# GB2530-K.net
KiCad netlist of a schematic drawn in Altium Designer
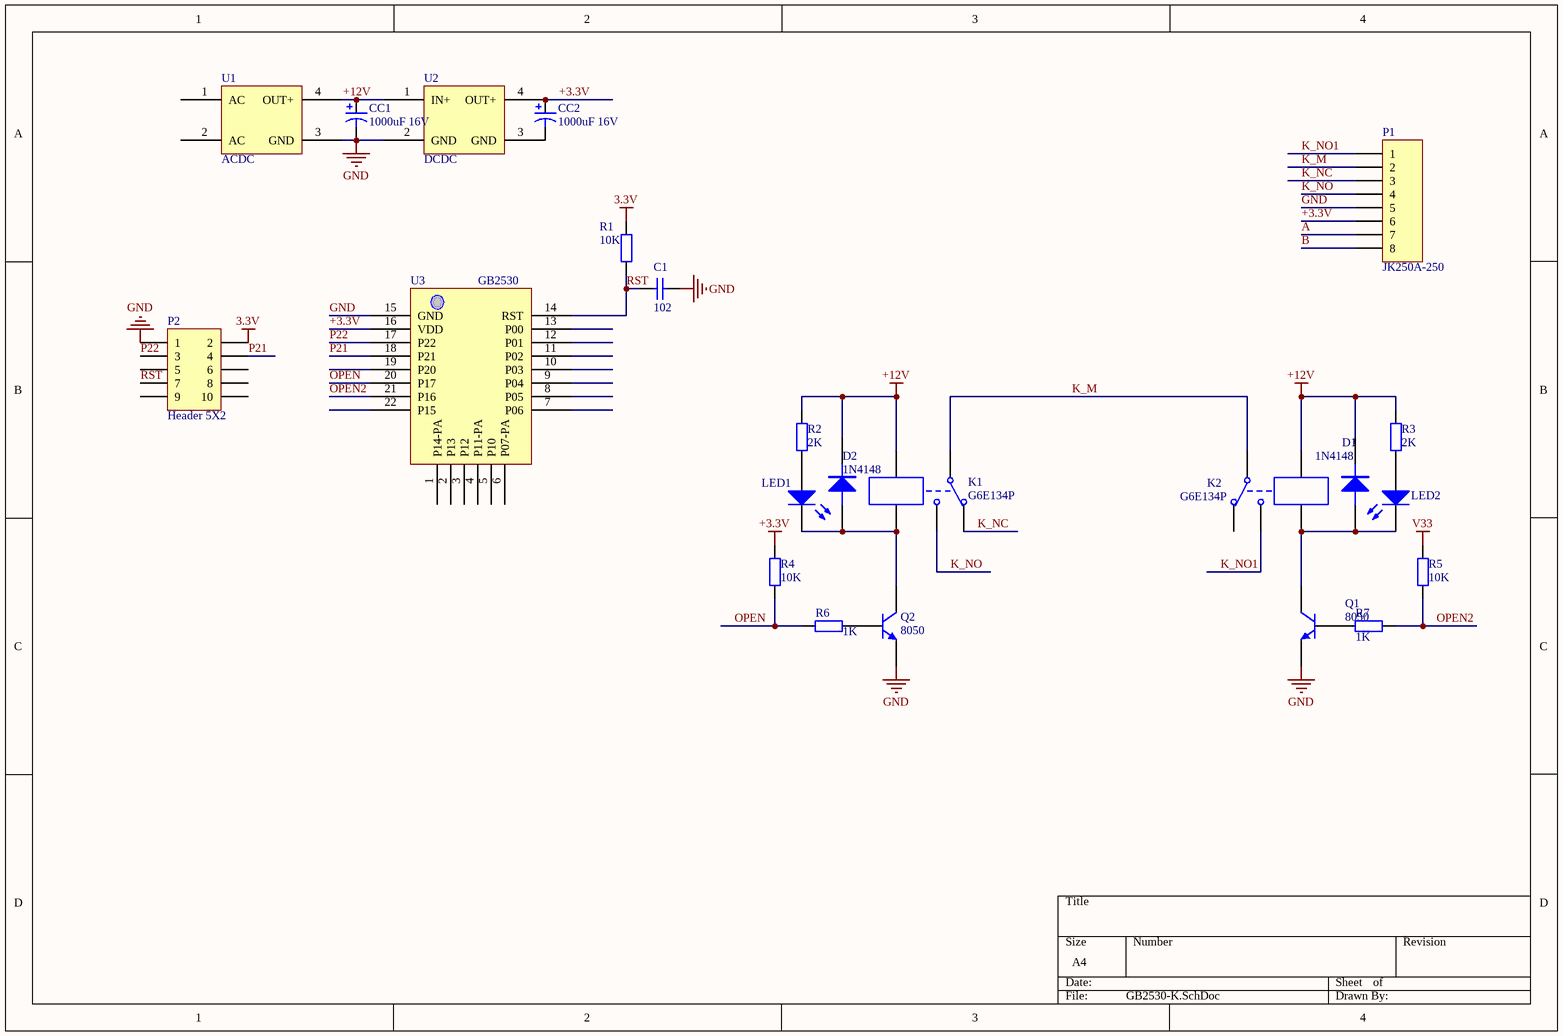
[diagram p0: GB2530-K.SchDoc]

(export (version "E")
  (design (tool "Eeschema 10.0.6"))
  (components
    (comp (ref "C1")
      (value "102")
      (footprint "0603")
      (description "Capacitor")
      (fields (field (name "Comment") "Cap") (field (name "PUBLISHER") "Altium Limited"))
      (libsource (lib "Miscellaneous Devices") (part "Cap"))
    )
    (comp (ref "CC1")
      (value "1000uF 16V")
      (footprint "C1010")
      (description "Polarized Capacitor (Radial)")
      (fields (field (name "Comment") "Cap Pol1") (field (name "PUBLISHER") "Altium Limited"))
      (libsource (lib "Miscellaneous Devices") (part "Cap Pol1"))
    )
    (comp (ref "CC2")
      (value "1000uF 16V")
      (footprint "C1010")
      (description "Polarized Capacitor (Radial)")
      (fields (field (name "Comment") "Cap Pol1") (field (name "PUBLISHER") "Altium Limited"))
      (libsource (lib "Miscellaneous Devices") (part "Cap Pol1"))
    )
    (comp (ref "D1")
      (value "1N4148")
      (footprint "DO-214AC - Diode")
      (description "Diode")
      (libsource (lib "*") (part "DIODE"))
    )
    (comp (ref "D2")
      (value "1N4148")
      (footprint "DO-214AC - Diode")
      (description "Diode")
      (libsource (lib "*") (part "DIODE"))
    )
    (comp (ref "K1")
      (value "G6E134P")
      (footprint "G6E134PUS")
      (description "Single-Pole Dual-Throw Relay")
      (fields (field (name "PUBLISHER") "Altium Limited"))
      (libsource (lib "Miscellaneous Devices") (part "Relay-SPDT"))
    )
    (comp (ref "K2")
      (value "G6E134P")
      (footprint "G6E134PUS")
      (description "Single-Pole Dual-Throw Relay")
      (fields (field (name "PUBLISHER") "Altium Limited"))
      (libsource (lib "Miscellaneous Devices") (part "Relay-SPDT"))
    )
    (comp (ref "LED1")
      (value "DS108")
      (footprint "LED0805")
      (description "Typical RED, GREEN, YELLOW, AMBER GaAs LED")
      (fields (field (name "PUBLISHER") "Altium Limited"))
      (libsource (lib "Miscellaneous Devices") (part "LED2"))
    )
    (comp (ref "LED2")
      (value "DS108")
      (footprint "LED0805")
      (description "Typical RED, GREEN, YELLOW, AMBER GaAs LED")
      (fields (field (name "PUBLISHER") "Altium Limited"))
      (libsource (lib "Miscellaneous Devices") (part "LED2"))
    )
    (comp (ref "P1")
      (value "JK250A-250")
      (footprint "KF250-2.5")
      (fields (field (name "PUBLISHER") "Altium Limited"))
      (libsource (lib "Miscellaneous Connectors") (part "Header 8"))
    )
    (comp (ref "P2")
      (value "Header 5X2")
      (footprint "HDR2X5")
      (description "Header, 5-Pin, Dual row")
      (fields (field (name "PUBLISHER") "Altium Limited"))
      (libsource (lib "Miscellaneous Connectors") (part "Header 5X2"))
    )
    (comp (ref "Q1")
      (value "8050")
      (footprint "SOT-23")
      (description "NPN General Purpose Amplifier")
      (fields (field (name "PUBLISHER") "Altium Limited"))
      (libsource (lib "Miscellaneous Devices") (part "2N3904"))
    )
    (comp (ref "Q2")
      (value "8050")
      (footprint "SOT-23")
      (description "NPN General Purpose Amplifier")
      (fields (field (name "PUBLISHER") "Altium Limited"))
      (libsource (lib "Miscellaneous Devices") (part "2N3904"))
    )
    (comp (ref "R1")
      (value "10K")
      (footprint "AXIAL-0.4")
      (description "Resistor")
      (fields (field (name "Comment") "Res2") (field (name "PUBLISHER") "Altium Limited"))
      (libsource (lib "") (part "Res2_2"))
    )
    (comp (ref "R2")
      (value "2K")
      (description "Resistor")
      (fields (field (name "PUBLISHER") "Altium Limited"))
      (libsource (lib "") (part "Res2_2"))
    )
    (comp (ref "R3")
      (value "2K")
      (description "Resistor")
      (fields (field (name "PUBLISHER") "Altium Limited"))
      (libsource (lib "") (part "Res2_1"))
    )
    (comp (ref "R4")
      (value "10K")
      (footprint "R0603")
      (description "Resistor")
      (fields
        (field (name "MANUFACTURER") "Generic Components")
        (field (name "PUBLISHER") "Altium Hobart Technology Centre")
      )
      (libsource (lib "Miscellaneous Devices") (part "Res2"))
    )
    (comp (ref "R5")
      (value "10K")
      (footprint "R0603")
      (description "Resistor")
      (fields
        (field (name "MANUFACTURER") "Generic Components")
        (field (name "PUBLISHER") "Altium Hobart Technology Centre")
      )
      (libsource (lib "") (part "Res2_3"))
    )
    (comp (ref "R6")
      (value "1K")
      (footprint "R0603")
      (description "Resistor")
      (fields
        (field (name "MANUFACTURER") "Generic Components")
        (field (name "PUBLISHER") "Altium Hobart Technology Centre")
      )
      (libsource (lib "") (part "Res2_3"))
    )
    (comp (ref "R7")
      (value "1K")
      (footprint "R0603")
      (description "Resistor")
      (fields
        (field (name "MANUFACTURER") "Generic Components")
        (field (name "PUBLISHER") "Altium Hobart Technology Centre")
      )
      (libsource (lib "") (part "Res2_2"))
    )
    (comp (ref "U1") (value "ACDC") (footprint "ACDC") (libsource (lib "mxj_wwy") (part "ACDC")))
    (comp (ref "U2") (value "DCDC") (footprint "DCDC") (libsource (lib "mxj_wwy") (part "DCDC")))
    (comp (ref "U3") (value "GB2530") (footprint "TT-2530") (libsource (lib "mxj_wwy") (part "GB2530")))
  )
  (nets
    (net (code "1") (name "+3.3V") (class "Default")
      (node (ref "CC2") (pin "1") (pinfunction "1_1") (pintype "passive"))
      (node (ref "P1") (pin "6") (pinfunction "6_6") (pintype "passive"))
      (node (ref "R4") (pin "1") (pinfunction "1_1") (pintype "passive"))
      (node (ref "U2") (pin "4") (pinfunction "OUT+_4") (pintype "passive"))
      (node (ref "U3") (pin "16") (pinfunction "VDD_16") (pintype "passive"))
    )
    (net (code "2") (name "+12V") (class "Default")
      (node (ref "CC1") (pin "1") (pinfunction "1_1") (pintype "passive"))
      (node (ref "D1") (pin "2") (pinfunction "K_2") (pintype "passive"))
      (node (ref "D2") (pin "2") (pinfunction "K_2") (pintype "passive"))
      (node (ref "K1") (pin "1") (pinfunction "1_1") (pintype "passive"))
      (node (ref "K2") (pin "1") (pinfunction "1_1") (pintype "passive"))
      (node (ref "R2") (pin "2") (pinfunction "2_2") (pintype "passive"))
      (node (ref "R3") (pin "2") (pinfunction "2_2") (pintype "passive"))
      (node (ref "U1") (pin "4") (pinfunction "OUT+_4") (pintype "passive"))
      (node (ref "U2") (pin "1") (pinfunction "IN+_1") (pintype "passive"))
    )
    (net (code "3") (name "/A") (class "Default")
      (node (ref "P1") (pin "7") (pinfunction "7_7") (pintype "passive"))
    )
    (net (code "4") (name "/B") (class "Default")
      (node (ref "P1") (pin "8") (pinfunction "8_8") (pintype "passive"))
    )
    (net (code "5") (name "/K_M") (class "Default")
      (node (ref "K1") (pin "7") (pinfunction "7_7") (pintype "passive"))
      (node (ref "K2") (pin "7") (pinfunction "7_7") (pintype "passive"))
      (node (ref "P1") (pin "2") (pinfunction "2_2") (pintype "passive"))
    )
    (net (code "6") (name "/K_NC") (class "Default")
      (node (ref "K1") (pin "10") (pinfunction "10_10") (pintype "passive"))
      (node (ref "P1") (pin "3") (pinfunction "3_3") (pintype "passive"))
    )
    (net (code "7") (name "/K_NO") (class "Default")
      (node (ref "K1") (pin "12") (pinfunction "12_12") (pintype "passive"))
      (node (ref "P1") (pin "4") (pinfunction "4_4") (pintype "passive"))
    )
    (net (code "8") (name "/K_NO1") (class "Default")
      (node (ref "K2") (pin "12") (pinfunction "12_12") (pintype "passive"))
      (node (ref "P1") (pin "1") (pinfunction "1_1") (pintype "passive"))
    )
    (net (code "9") (name "/OPEN") (class "Default")
      (node (ref "R4") (pin "2") (pinfunction "2_2") (pintype "passive"))
      (node (ref "R6") (pin "2") (pinfunction "2_2") (pintype "passive"))
      (node (ref "U3") (pin "20") (pinfunction "P17_20") (pintype "passive"))
    )
    (net (code "10") (name "/OPEN2") (class "Default")
      (node (ref "R5") (pin "2") (pinfunction "2_2") (pintype "passive"))
      (node (ref "R7") (pin "2") (pinfunction "2_2") (pintype "passive"))
      (node (ref "U3") (pin "21") (pinfunction "P16_21") (pintype "passive"))
    )
    (net (code "11") (name "/P21") (class "Default")
      (node (ref "P2") (pin "4") (pinfunction "4_4") (pintype "passive"))
      (node (ref "U3") (pin "18") (pinfunction "P21_18") (pintype "passive"))
    )
    (net (code "12") (name "/P22") (class "Default")
      (node (ref "P2") (pin "3") (pinfunction "3_3") (pintype "passive"))
      (node (ref "U3") (pin "17") (pinfunction "P22_17") (pintype "passive"))
    )
    (net (code "13") (name "/RST") (class "Default")
      (node (ref "C1") (pin "1") (pinfunction "1_1") (pintype "passive"))
      (node (ref "P2") (pin "7") (pinfunction "7_7") (pintype "passive"))
      (node (ref "R1") (pin "1") (pinfunction "1_1") (pintype "passive"))
      (node (ref "U3") (pin "14") (pinfunction "RST_14") (pintype "passive"))
    )
    (net (code "14") (name "3.3V") (class "Default")
      (node (ref "P2") (pin "2") (pinfunction "2_2") (pintype "passive"))
      (node (ref "R1") (pin "2") (pinfunction "2_2") (pintype "passive"))
    )
    (net (code "15") (name "GND") (class "Default")
      (node (ref "C1") (pin "2") (pinfunction "2_2") (pintype "passive"))
      (node (ref "CC1") (pin "2") (pinfunction "2_2") (pintype "passive"))
      (node (ref "P1") (pin "5") (pinfunction "5_5") (pintype "passive"))
      (node (ref "P2") (pin "1") (pinfunction "1_1") (pintype "passive"))
      (node (ref "Q1") (pin "2") (pinfunction "E_2") (pintype "passive"))
      (node (ref "Q2") (pin "2") (pinfunction "E_2") (pintype "passive"))
      (node (ref "U1") (pin "3") (pinfunction "GND_3") (pintype "passive"))
      (node (ref "U2") (pin "2") (pinfunction "GND_2") (pintype "passive"))
      (node (ref "U3") (pin "15") (pinfunction "GND_15") (pintype "passive"))
    )
    (net (code "16") (name "Net-(CC2-Pad2)") (class "Default")
      (node (ref "CC2") (pin "2") (pinfunction "2_2") (pintype "passive"))
      (node (ref "U2") (pin "3") (pinfunction "GND_3") (pintype "passive"))
    )
    (net (code "17") (name "Net-(D1-A)") (class "Default")
      (node (ref "D1") (pin "1") (pinfunction "A_1") (pintype "passive"))
      (node (ref "K2") (pin "6") (pinfunction "6_6") (pintype "passive"))
      (node (ref "LED2") (pin "2") (pinfunction "K_2") (pintype "passive"))
      (node (ref "Q1") (pin "3") (pinfunction "C_3") (pintype "passive"))
    )
    (net (code "18") (name "Net-(D2-A)") (class "Default")
      (node (ref "D2") (pin "1") (pinfunction "A_1") (pintype "passive"))
      (node (ref "K1") (pin "6") (pinfunction "6_6") (pintype "passive"))
      (node (ref "LED1") (pin "2") (pinfunction "K_2") (pintype "passive"))
      (node (ref "Q2") (pin "3") (pinfunction "C_3") (pintype "passive"))
    )
    (net (code "19") (name "Net-(LED1-A)") (class "Default")
      (node (ref "LED1") (pin "1") (pinfunction "A_1") (pintype "passive"))
      (node (ref "R2") (pin "1") (pinfunction "1_1") (pintype "passive"))
    )
    (net (code "20") (name "Net-(LED2-A)") (class "Default")
      (node (ref "LED2") (pin "1") (pinfunction "A_1") (pintype "passive"))
      (node (ref "R3") (pin "1") (pinfunction "1_1") (pintype "passive"))
    )
    (net (code "21") (name "Net-(Q1-B)") (class "Default")
      (node (ref "Q1") (pin "1") (pinfunction "B_1") (pintype "passive"))
      (node (ref "R7") (pin "1") (pinfunction "1_1") (pintype "passive"))
    )
    (net (code "22") (name "Net-(Q2-B)") (class "Default")
      (node (ref "Q2") (pin "1") (pinfunction "B_1") (pintype "passive"))
      (node (ref "R6") (pin "1") (pinfunction "1_1") (pintype "passive"))
    )
    (net (code "23") (name "V33") (class "Default")
      (node (ref "R5") (pin "1") (pinfunction "1_1") (pintype "passive"))
    )
    (net (code "24") (name "unconnected-(K2-Pad10)") (class "Default")
      (node (ref "K2") (pin "10") (pinfunction "10_10") (pintype "passive"))
    )
    (net (code "25") (name "unconnected-(P2-Pad5)") (class "Default")
      (node (ref "P2") (pin "5") (pinfunction "5_5") (pintype "passive"))
    )
    (net (code "26") (name "unconnected-(P2-Pad6)") (class "Default")
      (node (ref "P2") (pin "6") (pinfunction "6_6") (pintype "passive"))
    )
    (net (code "27") (name "unconnected-(P2-Pad8)") (class "Default")
      (node (ref "P2") (pin "8") (pinfunction "8_8") (pintype "passive"))
    )
    (net (code "28") (name "unconnected-(P2-Pad9)") (class "Default")
      (node (ref "P2") (pin "9") (pinfunction "9_9") (pintype "passive"))
    )
    (net (code "29") (name "unconnected-(P2-Pad10)") (class "Default")
      (node (ref "P2") (pin "10") (pinfunction "10_10") (pintype "passive"))
    )
    (net (code "30") (name "unconnected-(U1-AC-Pad1)") (class "Default")
      (node (ref "U1") (pin "1") (pinfunction "AC_1") (pintype "passive"))
    )
    (net (code "31") (name "unconnected-(U1-AC-Pad2)") (class "Default")
      (node (ref "U1") (pin "2") (pinfunction "AC_2") (pintype "passive"))
    )
    (net (code "32") (name "unconnected-(U3-P00-Pad13)") (class "Default")
      (node (ref "U3") (pin "13") (pinfunction "P00_13") (pintype "passive"))
    )
    (net (code "33") (name "unconnected-(U3-P01-Pad12)") (class "Default")
      (node (ref "U3") (pin "12") (pinfunction "P01_12") (pintype "passive"))
    )
    (net (code "34") (name "unconnected-(U3-P02-Pad11)") (class "Default")
      (node (ref "U3") (pin "11") (pinfunction "P02_11") (pintype "passive"))
    )
    (net (code "35") (name "unconnected-(U3-P03-Pad10)") (class "Default")
      (node (ref "U3") (pin "10") (pinfunction "P03_10") (pintype "passive"))
    )
    (net (code "36") (name "unconnected-(U3-P04-Pad9)") (class "Default")
      (node (ref "U3") (pin "9") (pinfunction "P04_9") (pintype "passive"))
    )
    (net (code "37") (name "unconnected-(U3-P05-Pad8)") (class "Default")
      (node (ref "U3") (pin "8") (pinfunction "P05_8") (pintype "passive"))
    )
    (net (code "38") (name "unconnected-(U3-P06-Pad7)") (class "Default")
      (node (ref "U3") (pin "7") (pinfunction "P06_7") (pintype "passive"))
    )
    (net (code "39") (name "unconnected-(U3-P07-PA-Pad6)") (class "Default")
      (node (ref "U3") (pin "6") (pinfunction "P07-PA_6") (pintype "passive"))
    )
    (net (code "40") (name "unconnected-(U3-P10-Pad5)") (class "Default")
      (node (ref "U3") (pin "5") (pinfunction "P10_5") (pintype "passive"))
    )
    (net (code "41") (name "unconnected-(U3-P11-PA-Pad4)") (class "Default")
      (node (ref "U3") (pin "4") (pinfunction "P11-PA_4") (pintype "passive"))
    )
    (net (code "42") (name "unconnected-(U3-P12-Pad3)") (class "Default")
      (node (ref "U3") (pin "3") (pinfunction "P12_3") (pintype "passive"))
    )
    (net (code "43") (name "unconnected-(U3-P13-Pad2)") (class "Default")
      (node (ref "U3") (pin "2") (pinfunction "P13_2") (pintype "passive"))
    )
    (net (code "44") (name "unconnected-(U3-P14-PA-Pad1)") (class "Default")
      (node (ref "U3") (pin "1") (pinfunction "P14-PA_1") (pintype "passive"))
    )
    (net (code "45") (name "unconnected-(U3-P15-Pad22)") (class "Default")
      (node (ref "U3") (pin "22") (pinfunction "P15_22") (pintype "passive"))
    )
    (net (code "46") (name "unconnected-(U3-P20-Pad19)") (class "Default")
      (node (ref "U3") (pin "19") (pinfunction "P20_19") (pintype "passive"))
    )
  )
)
